# pic16f1829_for_JRTU-EV17.net
KiCad netlist of a schematic drawn in EAGLE
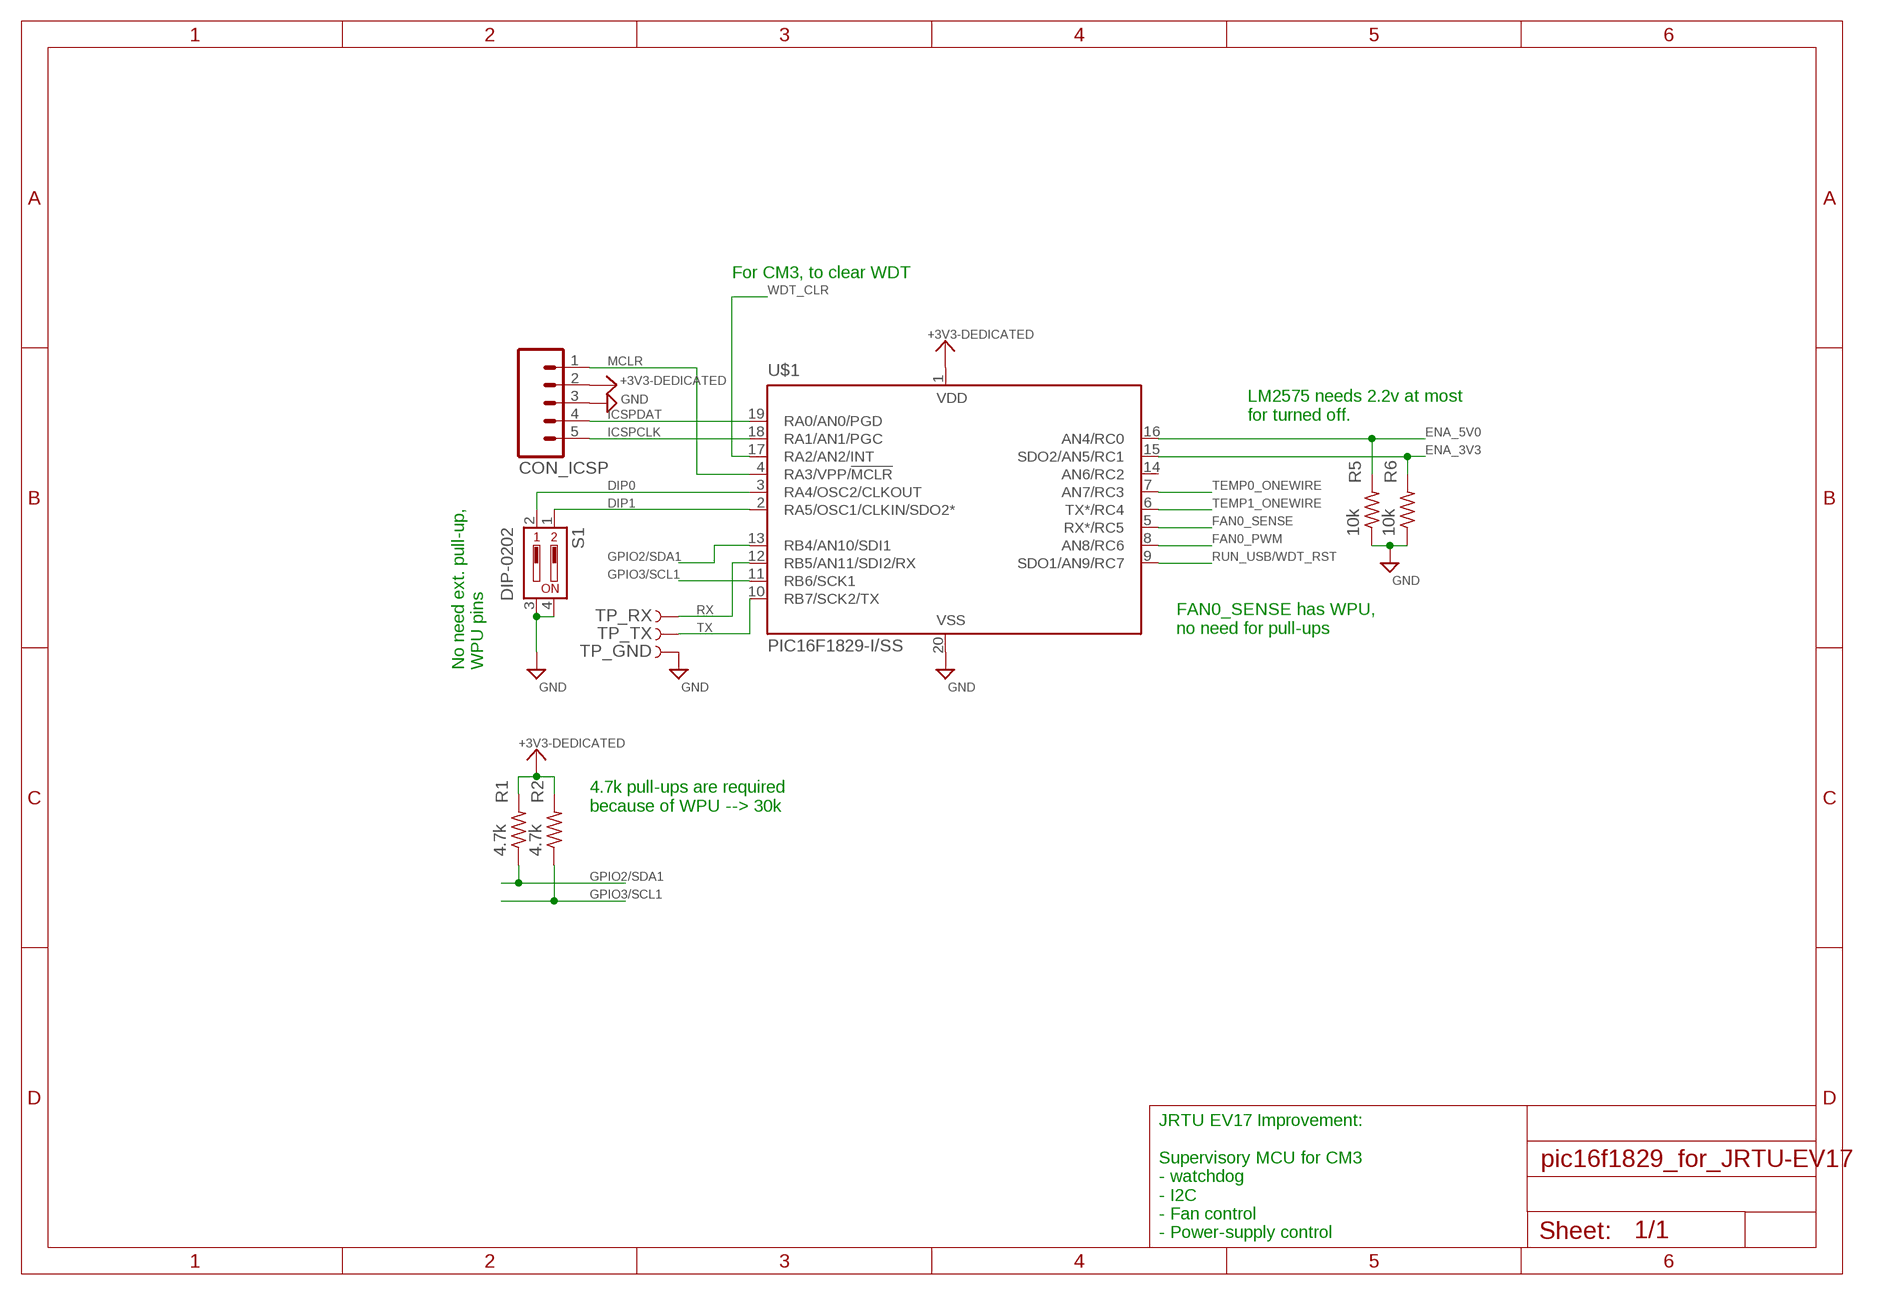
[diagram p0: schematic, sheet 1]

(export (version "E")
  (design (tool "Eeschema 10.0.6"))
  (components
    (comp (ref "CON_ICSP")
      (value "M05")
      (footprint "eagle-import:1X05")
      (libsource (lib "eagle-import") (part "M05"))
    )
    (comp (ref "R1")
      (value "4.7k")
      (footprint "eagle-import:RCL_M0805")
      (libsource (lib "eagle-import") (part "RCL_R-USM0805"))
    )
    (comp (ref "R2")
      (value "4.7k")
      (footprint "eagle-import:RCL_M0805")
      (libsource (lib "eagle-import") (part "RCL_R-USM0805"))
    )
    (comp (ref "R5")
      (value "10k")
      (footprint "eagle-import:RCL_M0805")
      (libsource (lib "eagle-import") (part "RCL_R-USM0805"))
    )
    (comp (ref "R6")
      (value "10k")
      (footprint "eagle-import:RCL_M0805")
      (libsource (lib "eagle-import") (part "RCL_R-USM0805"))
    )
    (comp (ref "S1")
      (value "DIP-0202")
      (footprint "eagle-import:DIPSWITCH-02")
      (libsource (lib "eagle-import") (part "DIP-0202"))
    )
    (comp (ref "TP_GND")
      (value "TEST-POINT3")
      (footprint "eagle-import:PAD.03X.03")
      (libsource (lib "eagle-import") (part "TEST-POINT3"))
    )
    (comp (ref "TP_RX")
      (value "TEST-POINT3")
      (footprint "eagle-import:PAD.03X.03")
      (libsource (lib "eagle-import") (part "TEST-POINT3"))
    )
    (comp (ref "TP_TX")
      (value "TEST-POINT3")
      (footprint "eagle-import:PAD.03X.03")
      (libsource (lib "eagle-import") (part "TEST-POINT3"))
    )
    (comp (ref "U$1")
      (value "PIC16F1829-I/SS")
      (footprint "eagle-import:SSOP20")
      (libsource (lib "eagle-import") (part "PIC16F1829"))
    )
  )
  (nets
    (net (code "1") (name "+3V3-DEDICATED") (class "Default")
      (node (ref "CON_ICSP") (pin "2") (pinfunction "2_2") (pintype "passive"))
      (node (ref "R1") (pin "2") (pinfunction "2_2") (pintype "passive"))
      (node (ref "R2") (pin "2") (pinfunction "2_2") (pintype "passive"))
      (node (ref "U$1") (pin "1") (pinfunction "VDD_1") (pintype "power_in"))
    )
    (net (code "2") (name "/DIP0") (class "Default")
      (node (ref "S1") (pin "2") (pinfunction "P$2_2") (pintype "bidirectional"))
      (node (ref "U$1") (pin "3") (pinfunction "RA4/OSC2/CLKOUT_3") (pintype "bidirectional"))
    )
    (net (code "3") (name "/DIP1") (class "Default")
      (node (ref "S1") (pin "1") (pinfunction "P$1_1") (pintype "bidirectional"))
      (node (ref "U$1") (pin "2") (pinfunction "RA5/OSC1/CLKIN/SDO2*_2") (pintype "bidirectional"))
    )
    (net (code "4") (name "/ENA_3V3") (class "Default")
      (node (ref "R6") (pin "2") (pinfunction "2_2") (pintype "passive"))
      (node (ref "U$1") (pin "15") (pinfunction "SDO2/AN5/RC1_15") (pintype "bidirectional"))
    )
    (net (code "5") (name "/ENA_5V0") (class "Default")
      (node (ref "R5") (pin "2") (pinfunction "2_2") (pintype "passive"))
      (node (ref "U$1") (pin "16") (pinfunction "AN4/RC0_16") (pintype "bidirectional"))
    )
    (net (code "6") (name "/FAN0_PWM") (class "Default")
      (node (ref "U$1") (pin "8") (pinfunction "AN8/RC6_8") (pintype "bidirectional"))
    )
    (net (code "7") (name "/FAN0_SENSE") (class "Default")
      (node (ref "U$1") (pin "5") (pinfunction "RX*/RC5_5") (pintype "bidirectional"))
    )
    (net (code "8") (name "/GPIO2{slash}SDA1") (class "Default")
      (node (ref "R1") (pin "1") (pinfunction "1_1") (pintype "passive"))
      (node (ref "U$1") (pin "13") (pinfunction "RB4/AN10/SDI1_13") (pintype "bidirectional"))
    )
    (net (code "9") (name "/GPIO3{slash}SCL1") (class "Default")
      (node (ref "R2") (pin "1") (pinfunction "1_1") (pintype "passive"))
      (node (ref "U$1") (pin "11") (pinfunction "RB6/SCK1_11") (pintype "bidirectional"))
    )
    (net (code "10") (name "/ICSPCLK") (class "Default")
      (node (ref "CON_ICSP") (pin "5") (pinfunction "5_5") (pintype "passive"))
      (node (ref "U$1") (pin "18") (pinfunction "RA1/AN1/PGC_18") (pintype "bidirectional"))
    )
    (net (code "11") (name "/ICSPDAT") (class "Default")
      (node (ref "CON_ICSP") (pin "4") (pinfunction "4_4") (pintype "passive"))
      (node (ref "U$1") (pin "19") (pinfunction "RA0/AN0/PGD_19") (pintype "bidirectional"))
    )
    (net (code "12") (name "/MCLR") (class "Default")
      (node (ref "CON_ICSP") (pin "1") (pinfunction "1_1") (pintype "passive"))
      (node (ref "U$1") (pin "4") (pinfunction "RA3/VPP/~{MCLR}_4") (pintype "input"))
    )
    (net (code "13") (name "/RUN_USB{slash}WDT_RST") (class "Default")
      (node (ref "U$1") (pin "9") (pinfunction "SDO1/AN9/RC7_9") (pintype "bidirectional"))
    )
    (net (code "14") (name "/RX") (class "Default")
      (node (ref "TP_RX") (pin "P$1") (pinfunction "1_P$1") (pintype "bidirectional"))
      (node (ref "U$1") (pin "12") (pinfunction "RB5/AN11/SDI2/RX_12") (pintype "bidirectional"))
    )
    (net (code "15") (name "/TEMP0_ONEWIRE") (class "Default")
      (node (ref "U$1") (pin "7") (pinfunction "AN7/RC3_7") (pintype "bidirectional"))
    )
    (net (code "16") (name "/TEMP1_ONEWIRE") (class "Default")
      (node (ref "U$1") (pin "6") (pinfunction "TX*/RC4_6") (pintype "bidirectional"))
    )
    (net (code "17") (name "/TX") (class "Default")
      (node (ref "TP_TX") (pin "P$1") (pinfunction "1_P$1") (pintype "bidirectional"))
      (node (ref "U$1") (pin "10") (pinfunction "RB7/SCK2/TX_10") (pintype "bidirectional"))
    )
    (net (code "18") (name "/WDT_CLR") (class "Default")
      (node (ref "U$1") (pin "17") (pinfunction "RA2/AN2/INT_17") (pintype "bidirectional"))
    )
    (net (code "19") (name "GND") (class "Default")
      (node (ref "CON_ICSP") (pin "3") (pinfunction "3_3") (pintype "passive"))
      (node (ref "R5") (pin "1") (pinfunction "1_1") (pintype "passive"))
      (node (ref "R6") (pin "1") (pinfunction "1_1") (pintype "passive"))
      (node (ref "S1") (pin "3") (pinfunction "P$3_3") (pintype "bidirectional"))
      (node (ref "S1") (pin "4") (pinfunction "P$4_4") (pintype "bidirectional"))
      (node (ref "TP_GND") (pin "P$1") (pinfunction "1_P$1") (pintype "bidirectional"))
      (node (ref "U$1") (pin "20") (pinfunction "VSS_20") (pintype "power_in"))
    )
    (net (code "20") (name "unconnected-(U$1-AN6{slash}RC2-Pad14)") (class "Default")
      (node (ref "U$1") (pin "14") (pinfunction "AN6/RC2_14") (pintype "bidirectional"))
    )
  )
)
